# Main.net
KiCad netlist of a schematic drawn in Altium Designer
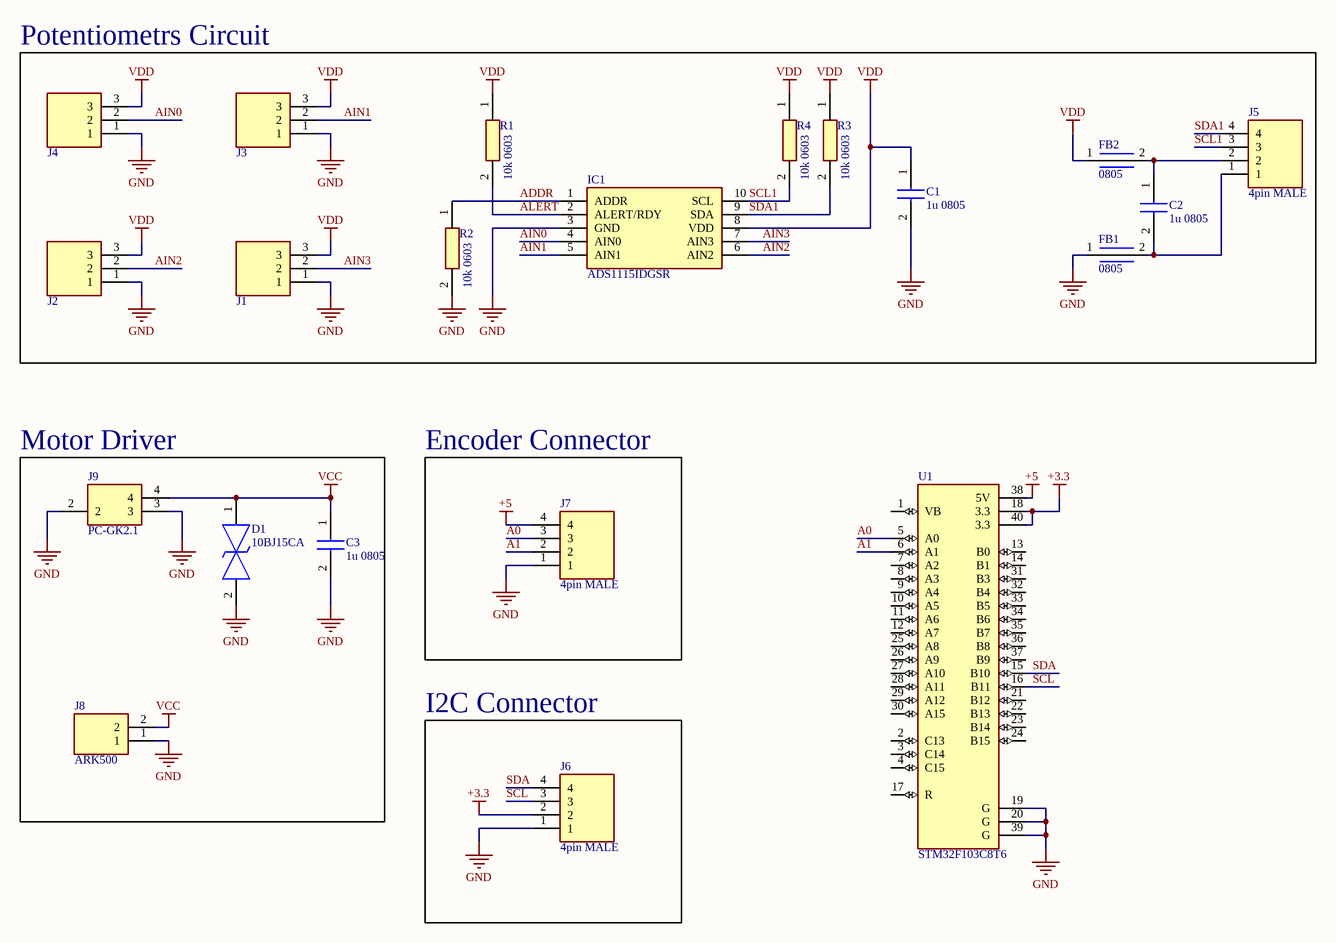
[diagram p0: Main.SchDoc]

(export (version "E")
  (design (tool "Eeschema 10.0.6"))
  (components
    (comp (ref "C1")
      (value "1u 0805")
      (footprint "SamacSys:CAPC2012X135N")
      (description "Capacitor")
      (fields
        (field (name "MANUFACTURER_PART_NUMBER") "CL21B105KBFNNNE")
        (field (name "MOUSER PART NUMBER") "187-CL21B105KBFNNNE")
      )
      (libsource (lib "*") (part "CL21B105KBFNNNE"))
    )
    (comp (ref "C2")
      (value "1u 0805")
      (footprint "SamacSys:CAPC2012X135N")
      (description "Capacitor")
      (fields
        (field (name "MANUFACTURER_PART_NUMBER") "CL21B105KBFNNNE")
        (field (name "MOUSER PART NUMBER") "187-CL21B105KBFNNNE")
      )
      (libsource (lib "*") (part "CL21B105KBFNNNE"))
    )
    (comp (ref "C3")
      (value "1u 0805")
      (footprint "SamacSys:CAPC2012X135N")
      (description "Capacitor")
      (fields
        (field (name "MANUFACTURER_PART_NUMBER") "CL21B105KBFNNNE")
        (field (name "MOUSER PART NUMBER") "187-CL21B105KBFNNNE")
      )
      (libsource (lib "*") (part "CL21B105KBFNNNE"))
    )
    (comp (ref "D1")
      (value "10BJ15CA")
      (footprint "SamacSys:10BJ15CA")
      (description "TVS Diode (Bi-directional)")
      (fields (field (name "MOUSER PART NUMBER") "504-10BJ15CA"))
      (libsource (lib "*") (part "10BJ15CA"))
    )
    (comp (ref "FB1")
      (value "0805")
      (footprint "SamacSys:MFBM1V2012102R")
      (description "Ferrite Bead")
      (fields (field (name "MANUFACTURER_PART_NUMBER") "MFBM1V2012-102-R"))
      (libsource (lib "SamacSys") (part "MFBM1V2012-102-R"))
    )
    (comp (ref "FB2")
      (value "0805")
      (footprint "SamacSys:MFBM1V2012102R")
      (description "Ferrite Bead")
      (fields (field (name "MANUFACTURER_PART_NUMBER") "MFBM1V2012-102-R"))
      (libsource (lib "SamacSys") (part "MFBM1V2012-102-R"))
    )
    (comp (ref "IC1")
      (value "ADS1115IDGSR")
      (footprint "SamacSys:SOP50P490X110-10N")
      (description "Integrated Circuit")
      (fields (field (name "MOUSER PART NUMBER") "595-ADS1115IDGSR"))
      (libsource (lib "*") (part "ADS1115IDGSR"))
    )
    (comp (ref "J1")
      (value "3pin MALE")
      (footprint "SamacSys:S3BPHKSLFSN")
      (description "Connector")
      (fields (field (name "MANUFACTURER_PART_NUMBER") "S3B-PH-K-S (LF)(SN)"))
      (libsource (lib "*") (part "S3B-PH-K-S__LF__SN_"))
    )
    (comp (ref "J2")
      (value "3pin MALE")
      (footprint "SamacSys:S3BPHKSLFSN")
      (description "Connector")
      (fields (field (name "MANUFACTURER_PART_NUMBER") "S3B-PH-K-S (LF)(SN)"))
      (libsource (lib "*") (part "S3B-PH-K-S__LF__SN_"))
    )
    (comp (ref "J3")
      (value "3pin MALE")
      (footprint "SamacSys:S3BPHKSLFSN")
      (description "Connector")
      (fields (field (name "MANUFACTURER_PART_NUMBER") "S3B-PH-K-S (LF)(SN)"))
      (libsource (lib "*") (part "S3B-PH-K-S__LF__SN_"))
    )
    (comp (ref "J4")
      (value "3pin MALE")
      (footprint "SamacSys:S3BPHKSLFSN")
      (description "Connector")
      (fields (field (name "MANUFACTURER_PART_NUMBER") "S3B-PH-K-S (LF)(SN)"))
      (libsource (lib "*") (part "S3B-PH-K-S__LF__SN_"))
    )
    (comp (ref "J5")
      (value "4pin MALE")
      (footprint "SamacSys:S4BPHKSLFSN")
      (description "Connector")
      (fields (field (name "MANUFACTURER_PART_NUMBER") "S4B-PH-K-S (LF)(SN)"))
      (libsource (lib "*") (part "S4B-PH-K-S__LF__SN_"))
    )
    (comp (ref "J6")
      (value "4pin MALE")
      (footprint "SamacSys:S4BPHKSLFSN")
      (description "Connector")
      (fields (field (name "MANUFACTURER_PART_NUMBER") "S4B-PH-K-S (LF)(SN)"))
      (libsource (lib "*") (part "S4B-PH-K-S__LF__SN_"))
    )
    (comp (ref "J7")
      (value "4pin MALE")
      (footprint "SamacSys:S4BPHKSLFSN")
      (description "Connector")
      (fields (field (name "MANUFACTURER_PART_NUMBER") "S4B-PH-K-S (LF)(SN)"))
      (libsource (lib "*") (part "S4B-PH-K-S__LF__SN_"))
    )
    (comp (ref "J8")
      (value "ARK500")
      (footprint "SamacSys:TB50P2PBL")
      (description "TB-5.0-P-2P_BL, Connector")
      (fields (field (name "MANUFACTURER_PART_NUMBER") "TB-5.0-P-2P/BL"))
      (libsource (lib "*") (part "TB-5.0-P-2P_BL"))
    )
    (comp (ref "J9")
      (value "PC-GK2.1")
      (footprint "SamacSys:PCGK21")
      (description "Connector")
      (libsource (lib "*") (part "PC-GK2.1"))
    )
    (comp (ref "R1")
      (value "10k 0603")
      (footprint "SamacSys:RESC1608X60N")
      (description "Resistor")
      (fields
        (field (name "MANUFACTURER_PART_NUMBER") "WR06X1002FTL")
        (field (name "MOUSER PART NUMBER") "791-WR06X1002FTL")
      )
      (libsource (lib "*") (part "WR06X1002FTL"))
    )
    (comp (ref "R2")
      (value "10k 0603")
      (footprint "SamacSys:RESC1608X60N")
      (description "Resistor")
      (fields
        (field (name "MANUFACTURER_PART_NUMBER") "WR06X1002FTL")
        (field (name "MOUSER PART NUMBER") "791-WR06X1002FTL")
      )
      (libsource (lib "*") (part "WR06X1002FTL"))
    )
    (comp (ref "R3")
      (value "10k 0603")
      (footprint "SamacSys:RESC1608X60N")
      (description "Resistor")
      (fields
        (field (name "MANUFACTURER_PART_NUMBER") "WR06X1002FTL")
        (field (name "MOUSER PART NUMBER") "791-WR06X1002FTL")
      )
      (libsource (lib "*") (part "WR06X1002FTL"))
    )
    (comp (ref "R4")
      (value "10k 0603")
      (footprint "SamacSys:RESC1608X60N")
      (description "Resistor")
      (fields
        (field (name "MANUFACTURER_PART_NUMBER") "WR06X1002FTL")
        (field (name "MOUSER PART NUMBER") "791-WR06X1002FTL")
      )
      (libsource (lib "*") (part "WR06X1002FTL"))
    )
    (comp (ref "U1")
      (value "STM32F103C8T6")
      (footprint "MODULE_ZC323000")
      (description "STM32F103C8T6 ARM STM32 Minimum System Development Board Module For Arduino")
      (fields (field (name "MP") "ZC323000"))
      (libsource (lib "Yevhen Shpatakov") (part "ZC323000"))
    )
  )
  (nets
    (net (code "1") (name "+3.3") (class "Default")
      (node (ref "J6") (pin "2") (pinfunction "2_2") (pintype "passive"))
      (node (ref "U1") (pin "18") (pinfunction "3.3_18") (pintype "power_in"))
      (node (ref "U1") (pin "40") (pinfunction "3.3_40") (pintype "power_in"))
    )
    (net (code "2") (name "+5") (class "Default")
      (node (ref "J7") (pin "4") (pinfunction "4_4") (pintype "passive"))
      (node (ref "U1") (pin "38") (pinfunction "5V_38") (pintype "power_in"))
    )
    (net (code "3") (name "/A0") (class "Default")
      (node (ref "J7") (pin "3") (pinfunction "3_3") (pintype "passive"))
      (node (ref "U1") (pin "5") (pinfunction "A0_5") (pintype "bidirectional"))
    )
    (net (code "4") (name "/A1") (class "Default")
      (node (ref "J7") (pin "2") (pinfunction "2_2") (pintype "passive"))
      (node (ref "U1") (pin "6") (pinfunction "A1_6") (pintype "bidirectional"))
    )
    (net (code "5") (name "/ADDR") (class "Default")
      (node (ref "IC1") (pin "1") (pinfunction "ADDR_1") (pintype "passive"))
      (node (ref "R2") (pin "1") (pinfunction "1_1") (pintype "passive"))
    )
    (net (code "6") (name "/AIN0") (class "Default")
      (node (ref "IC1") (pin "4") (pinfunction "AIN0_4") (pintype "passive"))
      (node (ref "J4") (pin "2") (pinfunction "2_2") (pintype "passive"))
    )
    (net (code "7") (name "/AIN1") (class "Default")
      (node (ref "IC1") (pin "5") (pinfunction "AIN1_5") (pintype "passive"))
      (node (ref "J3") (pin "2") (pinfunction "2_2") (pintype "passive"))
    )
    (net (code "8") (name "/AIN2") (class "Default")
      (node (ref "IC1") (pin "6") (pinfunction "AIN2_6") (pintype "passive"))
      (node (ref "J2") (pin "2") (pinfunction "2_2") (pintype "passive"))
    )
    (net (code "9") (name "/AIN3") (class "Default")
      (node (ref "IC1") (pin "7") (pinfunction "AIN3_7") (pintype "passive"))
      (node (ref "J1") (pin "2") (pinfunction "2_2") (pintype "passive"))
    )
    (net (code "10") (name "/ALERT") (class "Default")
      (node (ref "IC1") (pin "2") (pinfunction "ALERT/RDY_2") (pintype "passive"))
      (node (ref "R1") (pin "2") (pinfunction "2_2") (pintype "passive"))
    )
    (net (code "11") (name "/SCL") (class "Default")
      (node (ref "J6") (pin "3") (pinfunction "3_3") (pintype "passive"))
      (node (ref "U1") (pin "16") (pinfunction "B11_16") (pintype "bidirectional"))
    )
    (net (code "12") (name "/SCL1") (class "Default")
      (node (ref "IC1") (pin "10") (pinfunction "SCL_10") (pintype "passive"))
      (node (ref "J5") (pin "3") (pinfunction "3_3") (pintype "passive"))
      (node (ref "R4") (pin "2") (pinfunction "2_2") (pintype "passive"))
    )
    (net (code "13") (name "/SDA") (class "Default")
      (node (ref "J6") (pin "4") (pinfunction "4_4") (pintype "passive"))
      (node (ref "U1") (pin "15") (pinfunction "B10_15") (pintype "bidirectional"))
    )
    (net (code "14") (name "/SDA1") (class "Default")
      (node (ref "IC1") (pin "9") (pinfunction "SDA_9") (pintype "passive"))
      (node (ref "J5") (pin "4") (pinfunction "4_4") (pintype "passive"))
      (node (ref "R3") (pin "2") (pinfunction "2_2") (pintype "passive"))
    )
    (net (code "15") (name "GND") (class "Default")
      (node (ref "C1") (pin "2") (pinfunction "2_2") (pintype "passive"))
      (node (ref "C3") (pin "2") (pinfunction "2_2") (pintype "passive"))
      (node (ref "D1") (pin "2") (pinfunction "2_2") (pintype "passive"))
      (node (ref "FB1") (pin "1") (pinfunction "1_1") (pintype "passive"))
      (node (ref "IC1") (pin "3") (pinfunction "GND_3") (pintype "passive"))
      (node (ref "J1") (pin "1") (pinfunction "1_1") (pintype "passive"))
      (node (ref "J2") (pin "1") (pinfunction "1_1") (pintype "passive"))
      (node (ref "J3") (pin "1") (pinfunction "1_1") (pintype "passive"))
      (node (ref "J4") (pin "1") (pinfunction "1_1") (pintype "passive"))
      (node (ref "J6") (pin "1") (pinfunction "1_1") (pintype "passive"))
      (node (ref "J7") (pin "1") (pinfunction "1_1") (pintype "passive"))
      (node (ref "J8") (pin "1") (pinfunction "1_1") (pintype "passive"))
      (node (ref "J9") (pin "2") (pinfunction "2_2") (pintype "passive"))
      (node (ref "J9") (pin "3") (pinfunction "3_3") (pintype "passive"))
      (node (ref "R2") (pin "2") (pinfunction "2_2") (pintype "passive"))
      (node (ref "U1") (pin "19") (pinfunction "G_19") (pintype "power_in"))
      (node (ref "U1") (pin "20") (pinfunction "G_20") (pintype "power_in"))
      (node (ref "U1") (pin "39") (pinfunction "G_39") (pintype "power_in"))
    )
    (net (code "16") (name "Net-(C2-Pad1)") (class "Default")
      (node (ref "C2") (pin "1") (pinfunction "1_1") (pintype "passive"))
      (node (ref "FB2") (pin "2") (pinfunction "2_2") (pintype "passive"))
      (node (ref "J5") (pin "2") (pinfunction "2_2") (pintype "passive"))
    )
    (net (code "17") (name "Net-(C2-Pad2)") (class "Default")
      (node (ref "C2") (pin "2") (pinfunction "2_2") (pintype "passive"))
      (node (ref "FB1") (pin "2") (pinfunction "2_2") (pintype "passive"))
      (node (ref "J5") (pin "1") (pinfunction "1_1") (pintype "passive"))
    )
    (net (code "18") (name "VCC") (class "Default")
      (node (ref "C3") (pin "1") (pinfunction "1_1") (pintype "passive"))
      (node (ref "D1") (pin "1") (pinfunction "1_1") (pintype "passive"))
      (node (ref "J8") (pin "2") (pinfunction "2_2") (pintype "passive"))
      (node (ref "J9") (pin "4") (pinfunction "4_4") (pintype "passive"))
    )
    (net (code "19") (name "VDD") (class "Default")
      (node (ref "C1") (pin "1") (pinfunction "1_1") (pintype "passive"))
      (node (ref "FB2") (pin "1") (pinfunction "1_1") (pintype "passive"))
      (node (ref "IC1") (pin "8") (pinfunction "VDD_8") (pintype "passive"))
      (node (ref "J1") (pin "3") (pinfunction "3_3") (pintype "passive"))
      (node (ref "J2") (pin "3") (pinfunction "3_3") (pintype "passive"))
      (node (ref "J3") (pin "3") (pinfunction "3_3") (pintype "passive"))
      (node (ref "J4") (pin "3") (pinfunction "3_3") (pintype "passive"))
      (node (ref "R1") (pin "1") (pinfunction "1_1") (pintype "passive"))
      (node (ref "R3") (pin "1") (pinfunction "1_1") (pintype "passive"))
      (node (ref "R4") (pin "1") (pinfunction "1_1") (pintype "passive"))
    )
    (net (code "20") (name "unconnected-(U1-A2-Pad7)") (class "Default")
      (node (ref "U1") (pin "7") (pinfunction "A2_7") (pintype "bidirectional"))
    )
    (net (code "21") (name "unconnected-(U1-A3-Pad8)") (class "Default")
      (node (ref "U1") (pin "8") (pinfunction "A3_8") (pintype "bidirectional"))
    )
    (net (code "22") (name "unconnected-(U1-A4-Pad9)") (class "Default")
      (node (ref "U1") (pin "9") (pinfunction "A4_9") (pintype "bidirectional"))
    )
    (net (code "23") (name "unconnected-(U1-A5-Pad10)") (class "Default")
      (node (ref "U1") (pin "10") (pinfunction "A5_10") (pintype "bidirectional"))
    )
    (net (code "24") (name "unconnected-(U1-A6-Pad11)") (class "Default")
      (node (ref "U1") (pin "11") (pinfunction "A6_11") (pintype "bidirectional"))
    )
    (net (code "25") (name "unconnected-(U1-A7-Pad12)") (class "Default")
      (node (ref "U1") (pin "12") (pinfunction "A7_12") (pintype "bidirectional"))
    )
    (net (code "26") (name "unconnected-(U1-A8-Pad25)") (class "Default")
      (node (ref "U1") (pin "25") (pinfunction "A8_25") (pintype "bidirectional"))
    )
    (net (code "27") (name "unconnected-(U1-A9-Pad26)") (class "Default")
      (node (ref "U1") (pin "26") (pinfunction "A9_26") (pintype "bidirectional"))
    )
    (net (code "28") (name "unconnected-(U1-A10-Pad27)") (class "Default")
      (node (ref "U1") (pin "27") (pinfunction "A10_27") (pintype "bidirectional"))
    )
    (net (code "29") (name "unconnected-(U1-A11-Pad28)") (class "Default")
      (node (ref "U1") (pin "28") (pinfunction "A11_28") (pintype "bidirectional"))
    )
    (net (code "30") (name "unconnected-(U1-A12-Pad29)") (class "Default")
      (node (ref "U1") (pin "29") (pinfunction "A12_29") (pintype "bidirectional"))
    )
    (net (code "31") (name "unconnected-(U1-A15-Pad30)") (class "Default")
      (node (ref "U1") (pin "30") (pinfunction "A15_30") (pintype "bidirectional"))
    )
    (net (code "32") (name "unconnected-(U1-B0-Pad13)") (class "Default")
      (node (ref "U1") (pin "13") (pinfunction "B0_13") (pintype "bidirectional"))
    )
    (net (code "33") (name "unconnected-(U1-B1-Pad14)") (class "Default")
      (node (ref "U1") (pin "14") (pinfunction "B1_14") (pintype "bidirectional"))
    )
    (net (code "34") (name "unconnected-(U1-B3-Pad31)") (class "Default")
      (node (ref "U1") (pin "31") (pinfunction "B3_31") (pintype "bidirectional"))
    )
    (net (code "35") (name "unconnected-(U1-B4-Pad32)") (class "Default")
      (node (ref "U1") (pin "32") (pinfunction "B4_32") (pintype "bidirectional"))
    )
    (net (code "36") (name "unconnected-(U1-B5-Pad33)") (class "Default")
      (node (ref "U1") (pin "33") (pinfunction "B5_33") (pintype "bidirectional"))
    )
    (net (code "37") (name "unconnected-(U1-B6-Pad34)") (class "Default")
      (node (ref "U1") (pin "34") (pinfunction "B6_34") (pintype "bidirectional"))
    )
    (net (code "38") (name "unconnected-(U1-B7-Pad35)") (class "Default")
      (node (ref "U1") (pin "35") (pinfunction "B7_35") (pintype "bidirectional"))
    )
    (net (code "39") (name "unconnected-(U1-B8-Pad36)") (class "Default")
      (node (ref "U1") (pin "36") (pinfunction "B8_36") (pintype "bidirectional"))
    )
    (net (code "40") (name "unconnected-(U1-B9-Pad37)") (class "Default")
      (node (ref "U1") (pin "37") (pinfunction "B9_37") (pintype "bidirectional"))
    )
    (net (code "41") (name "unconnected-(U1-B12-Pad21)") (class "Default")
      (node (ref "U1") (pin "21") (pinfunction "B12_21") (pintype "bidirectional"))
    )
    (net (code "42") (name "unconnected-(U1-B13-Pad22)") (class "Default")
      (node (ref "U1") (pin "22") (pinfunction "B13_22") (pintype "bidirectional"))
    )
    (net (code "43") (name "unconnected-(U1-B14-Pad23)") (class "Default")
      (node (ref "U1") (pin "23") (pinfunction "B14_23") (pintype "bidirectional"))
    )
    (net (code "44") (name "unconnected-(U1-B15-Pad24)") (class "Default")
      (node (ref "U1") (pin "24") (pinfunction "B15_24") (pintype "bidirectional"))
    )
    (net (code "45") (name "unconnected-(U1-C13-Pad2)") (class "Default")
      (node (ref "U1") (pin "2") (pinfunction "C13_2") (pintype "bidirectional"))
    )
    (net (code "46") (name "unconnected-(U1-C14-Pad3)") (class "Default")
      (node (ref "U1") (pin "3") (pinfunction "C14_3") (pintype "bidirectional"))
    )
    (net (code "47") (name "unconnected-(U1-C15-Pad4)") (class "Default")
      (node (ref "U1") (pin "4") (pinfunction "C15_4") (pintype "bidirectional"))
    )
    (net (code "48") (name "unconnected-(U1-R-Pad17)") (class "Default")
      (node (ref "U1") (pin "17") (pinfunction "R_17") (pintype "bidirectional"))
    )
    (net (code "49") (name "unconnected-(U1-VB-Pad1)") (class "Default")
      (node (ref "U1") (pin "1") (pinfunction "VB_1") (pintype "bidirectional"))
    )
  )
)
